# Sheet1.net
KiCad netlist of a schematic drawn in Altium Designer
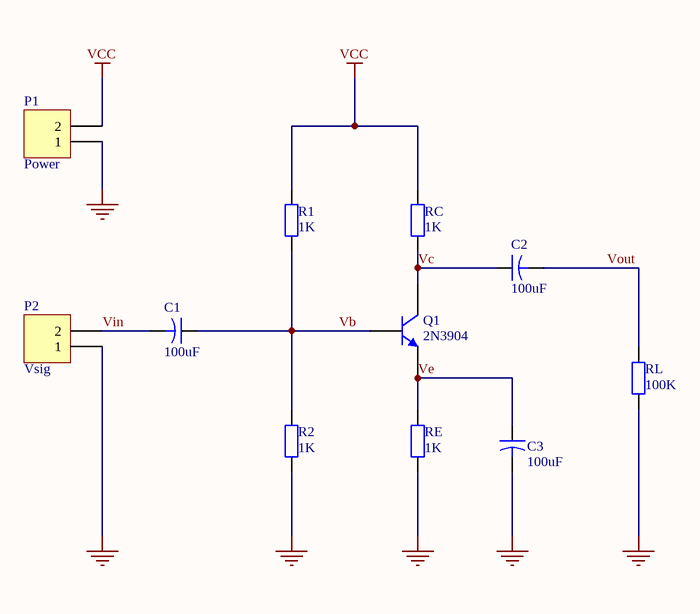
[diagram p0: Sheet1.SchDoc]

(export (version "E")
  (design (tool "Eeschema 10.0.6"))
  (components
    (comp (ref "C1")
      (value "100uF")
      (footprint "CAPR5-4X5")
      (description "Capacitor")
      (fields (field (name "Comment") "Cap2") (field (name "PUBLISHER") "Altium Limited"))
      (libsource (lib "Miscellaneous Devices") (part "Cap2"))
    )
    (comp (ref "C2")
      (value "100uF")
      (footprint "CAPR5-4X5")
      (description "Capacitor")
      (fields (field (name "Comment") "Cap2") (field (name "PUBLISHER") "Altium Limited"))
      (libsource (lib "Miscellaneous Devices") (part "Cap2"))
    )
    (comp (ref "C3")
      (value "100uF")
      (footprint "CAPR5-4X5")
      (description "Capacitor")
      (fields (field (name "Comment") "Cap2") (field (name "PUBLISHER") "Altium Limited"))
      (libsource (lib "Miscellaneous Devices") (part "Cap2"))
    )
    (comp (ref "P1")
      (value "Power")
      (footprint "HDR1X2")
      (description "Header, 2-Pin")
      (fields (field (name "PUBLISHER") "Altium Limited"))
      (libsource (lib "Miscellaneous Connectors") (part "Header 2"))
    )
    (comp (ref "P2")
      (value "Vsig")
      (footprint "HDR1X2")
      (description "Header, 2-Pin")
      (fields (field (name "PUBLISHER") "Altium Limited"))
      (libsource (lib "Miscellaneous Connectors") (part "Header 2"))
    )
    (comp (ref "Q1")
      (value "2N3904")
      (footprint "TO-92A")
      (description "NPN General Purpose Amplifier")
      (fields (field (name "PUBLISHER") "Altium Limited"))
      (libsource (lib "Miscellaneous Devices") (part "2N3904"))
    )
    (comp (ref "R1")
      (value "1K")
      (footprint "AXIAL-0.4")
      (description "Resistor")
      (fields (field (name "PUBLISHER") "Altium Limited"))
      (libsource (lib "Miscellaneous Devices") (part "Res2"))
    )
    (comp (ref "R2")
      (value "1K")
      (footprint "AXIAL-0.4")
      (description "Resistor")
      (fields (field (name "PUBLISHER") "Altium Limited"))
      (libsource (lib "Miscellaneous Devices") (part "Res2"))
    )
    (comp (ref "RC")
      (value "1K")
      (footprint "AXIAL-0.4")
      (description "Resistor")
      (fields (field (name "PUBLISHER") "Altium Limited"))
      (libsource (lib "Miscellaneous Devices") (part "Res2"))
    )
    (comp (ref "RE")
      (value "1K")
      (footprint "AXIAL-0.4")
      (description "Resistor")
      (fields (field (name "PUBLISHER") "Altium Limited"))
      (libsource (lib "Miscellaneous Devices") (part "Res2"))
    )
    (comp (ref "RL")
      (value "100K")
      (footprint "AXIAL-0.4")
      (description "Resistor")
      (fields (field (name "PUBLISHER") "Altium Limited"))
      (libsource (lib "Miscellaneous Devices") (part "Res2"))
    )
  )
  (nets
    (net (code "1") (name "/Vb") (class "Default")
      (node (ref "C1") (pin "1") (pinfunction "1_1") (pintype "passive"))
      (node (ref "Q1") (pin "2") (pinfunction "B_2") (pintype "passive"))
      (node (ref "R1") (pin "1") (pinfunction "1_1") (pintype "passive"))
      (node (ref "R2") (pin "2") (pinfunction "2_2") (pintype "passive"))
    )
    (net (code "2") (name "/Vc") (class "Default")
      (node (ref "C2") (pin "1") (pinfunction "1_1") (pintype "passive"))
      (node (ref "Q1") (pin "3") (pinfunction "C_3") (pintype "passive"))
      (node (ref "RC") (pin "1") (pinfunction "1_1") (pintype "passive"))
    )
    (net (code "3") (name "/Ve") (class "Default")
      (node (ref "C3") (pin "1") (pinfunction "1_1") (pintype "passive"))
      (node (ref "Q1") (pin "1") (pinfunction "E_1") (pintype "passive"))
      (node (ref "RE") (pin "2") (pinfunction "2_2") (pintype "passive"))
    )
    (net (code "4") (name "/Vin") (class "Default")
      (node (ref "C1") (pin "2") (pinfunction "2_2") (pintype "passive"))
      (node (ref "P2") (pin "2") (pinfunction "2_2") (pintype "passive"))
    )
    (net (code "5") (name "/Vout") (class "Default")
      (node (ref "C2") (pin "2") (pinfunction "2_2") (pintype "passive"))
      (node (ref "RL") (pin "2") (pinfunction "2_2") (pintype "passive"))
    )
    (net (code "6") (name "GND") (class "Default")
      (node (ref "C3") (pin "2") (pinfunction "2_2") (pintype "passive"))
      (node (ref "P1") (pin "1") (pinfunction "1_1") (pintype "passive"))
      (node (ref "P2") (pin "1") (pinfunction "1_1") (pintype "passive"))
      (node (ref "R2") (pin "1") (pinfunction "1_1") (pintype "passive"))
      (node (ref "RE") (pin "1") (pinfunction "1_1") (pintype "passive"))
      (node (ref "RL") (pin "1") (pinfunction "1_1") (pintype "passive"))
    )
    (net (code "7") (name "VCC") (class "Default")
      (node (ref "P1") (pin "2") (pinfunction "2_2") (pintype "passive"))
      (node (ref "R1") (pin "2") (pinfunction "2_2") (pintype "passive"))
      (node (ref "RC") (pin "2") (pinfunction "2_2") (pintype "passive"))
    )
  )
)
